# 03-VGA.net
KiCad netlist of a schematic drawn in Altium Designer
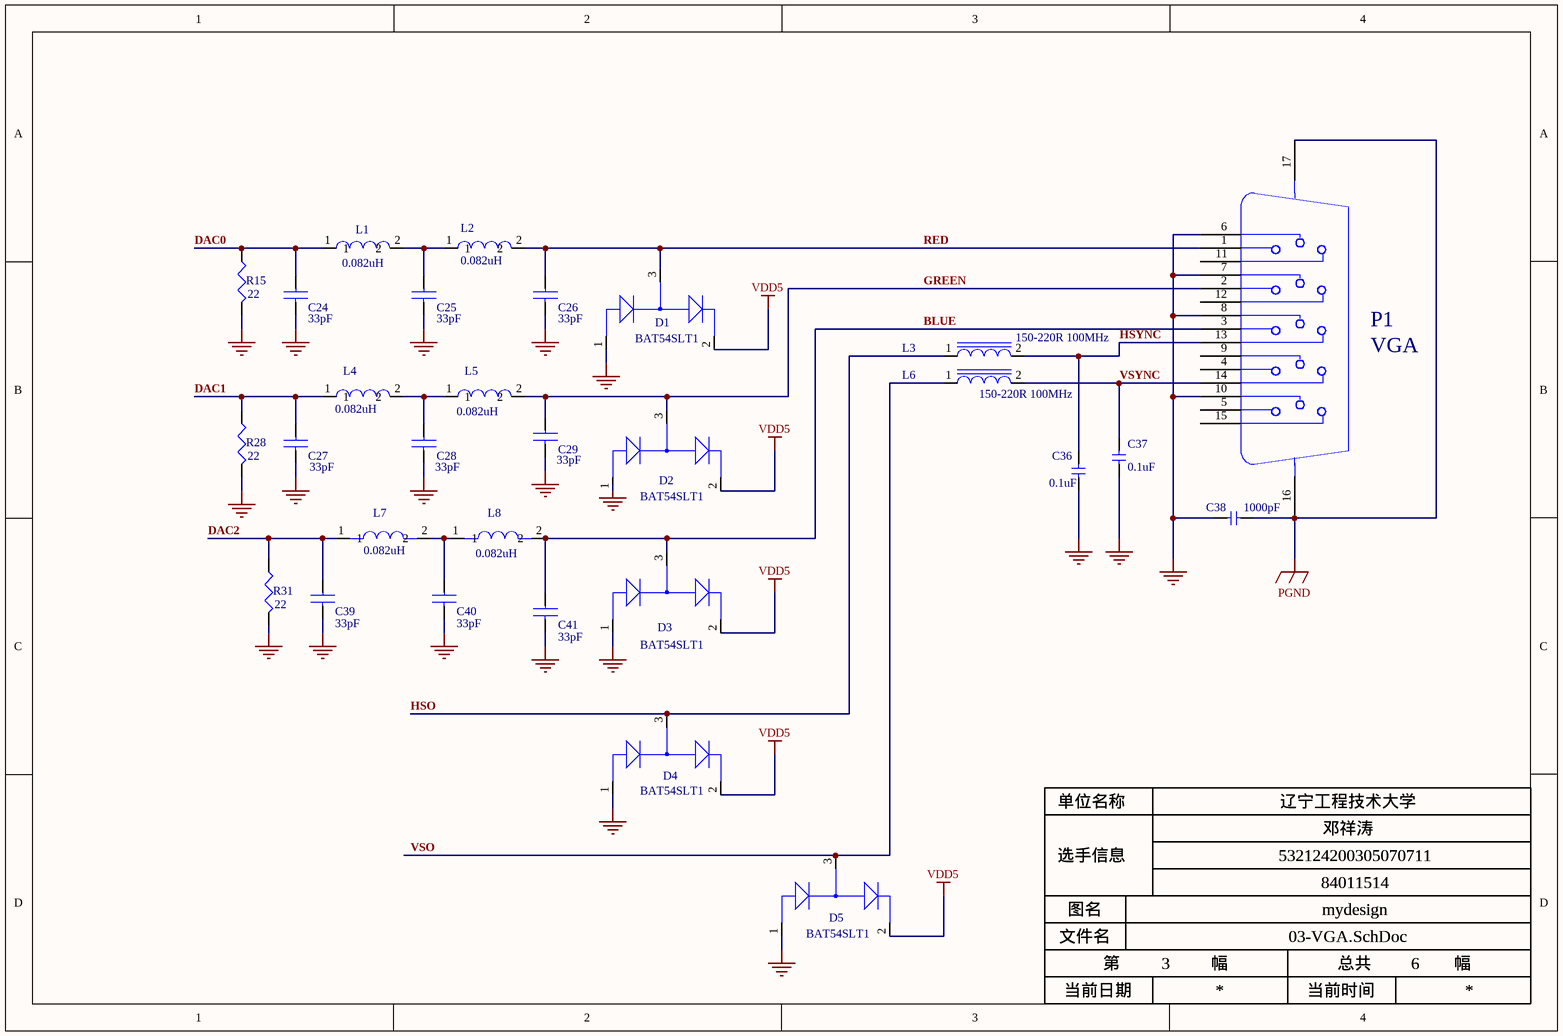
[diagram p0: 03-VGA.SchDoc]

(export (version "E")
  (design (tool "Eeschema 10.0.6"))
  (components
    (comp (ref "C24")
      (value "33pF")
      (footprint "C0603")
      (fields (field (name "Comment") "CAP"))
      (libsource (lib "VIDEO_Demo_Kit_1") (part "CAP"))
    )
    (comp (ref "C25")
      (value "33pF")
      (footprint "C0603")
      (fields (field (name "Comment") "CAP"))
      (libsource (lib "VIDEO_Demo_Kit_1") (part "CAP"))
    )
    (comp (ref "C26")
      (value "33pF")
      (footprint "C0603")
      (fields (field (name "Comment") "CAP"))
      (libsource (lib "VIDEO_Demo_Kit_1") (part "CAP"))
    )
    (comp (ref "C27")
      (value "33pF")
      (footprint "C0603")
      (fields (field (name "Comment") "CAP"))
      (libsource (lib "VIDEO_Demo_Kit_1") (part "CAP"))
    )
    (comp (ref "C28")
      (value "33pF")
      (footprint "C0603")
      (fields (field (name "Comment") "CAP"))
      (libsource (lib "VIDEO_Demo_Kit_1") (part "CAP"))
    )
    (comp (ref "C29")
      (value "33pF")
      (footprint "C0603")
      (fields (field (name "Comment") "CAP"))
      (libsource (lib "VIDEO_Demo_Kit_1") (part "CAP"))
    )
    (comp (ref "C36")
      (value "0.1uF")
      (footprint "C0603")
      (fields (field (name "VOLTAGE") "CMAX") (field (name "Comment") "C_2"))
      (libsource (lib "VIDEO_Demo_Kit_1") (part "C_2"))
    )
    (comp (ref "C37")
      (value "0.1uF")
      (footprint "C0603")
      (fields (field (name "VOLTAGE") "CMAX") (field (name "Comment") "C_2"))
      (libsource (lib "VIDEO_Demo_Kit_1") (part "C_2"))
    )
    (comp (ref "C38")
      (value "1000pF")
      (footprint "C0603")
      (fields (field (name "VOLTAGE") "CMAX") (field (name "Comment") "C_2"))
      (libsource (lib "VIDEO_Demo_Kit_1") (part "C_2"))
    )
    (comp (ref "C39")
      (value "33pF")
      (footprint "C0603")
      (fields (field (name "Comment") "CAP"))
      (libsource (lib "VIDEO_Demo_Kit_1") (part "CAP"))
    )
    (comp (ref "C40")
      (value "33pF")
      (footprint "C0603")
      (fields (field (name "Comment") "CAP"))
      (libsource (lib "VIDEO_Demo_Kit_1") (part "CAP"))
    )
    (comp (ref "C41")
      (value "33pF")
      (footprint "C0603")
      (fields (field (name "Comment") "CAP"))
      (libsource (lib "VIDEO_Demo_Kit_1") (part "CAP"))
    )
    (comp (ref "D1")
      (value "BAT54SLT1")
      (footprint "SOT-23")
      (fields (field (name "Comment") "DIODE_DUAL_SERIES_SOT23"))
      (libsource (lib "VIDEO_Demo_Kit_1") (part "DIODE_DUAL_SERIES_SOT23"))
    )
    (comp (ref "D2")
      (value "BAT54SLT1")
      (footprint "SOT-23")
      (fields (field (name "Comment") "DIODE_DUAL_SERIES_SOT23"))
      (libsource (lib "VIDEO_Demo_Kit_1") (part "DIODE_DUAL_SERIES_SOT23"))
    )
    (comp (ref "D3")
      (value "BAT54SLT1")
      (footprint "SOT-23")
      (fields (field (name "Comment") "DIODE_DUAL_SERIES_SOT23"))
      (libsource (lib "VIDEO_Demo_Kit_1") (part "DIODE_DUAL_SERIES_SOT23"))
    )
    (comp (ref "D4")
      (value "BAT54SLT1")
      (footprint "SOT-23")
      (fields (field (name "Comment") "DIODE_DUAL_SERIES_SOT23"))
      (libsource (lib "VIDEO_Demo_Kit_1") (part "DIODE_DUAL_SERIES_SOT23"))
    )
    (comp (ref "D5")
      (value "BAT54SLT1")
      (footprint "SOT-23")
      (fields (field (name "Comment") "DIODE_DUAL_SERIES_SOT23"))
      (libsource (lib "VIDEO_Demo_Kit_1") (part "DIODE_DUAL_SERIES_SOT23"))
    )
    (comp (ref "L1")
      (value "0.082uH")
      (footprint "0805-l")
      (fields (field (name "Comment") "L"))
      (libsource (lib "*") (part "L"))
    )
    (comp (ref "L2")
      (value "0.082uH")
      (footprint "0805-l")
      (fields (field (name "Comment") "L"))
      (libsource (lib "*") (part "L"))
    )
    (comp (ref "L3")
      (value "150-220R 100MHz")
      (footprint "0805-l")
      (fields (field (name "Comment") "L_0"))
      (libsource (lib "VIDEO_Demo_Kit_1") (part "L_0"))
    )
    (comp (ref "L4")
      (value "0.082uH")
      (footprint "0805-l")
      (fields (field (name "Comment") "L"))
      (libsource (lib "*") (part "L"))
    )
    (comp (ref "L5")
      (value "0.082uH")
      (footprint "0805-l")
      (fields (field (name "Comment") "L"))
      (libsource (lib "*") (part "L"))
    )
    (comp (ref "L6")
      (value "150-220R 100MHz")
      (footprint "0805-l")
      (fields (field (name "Comment") "L_0"))
      (libsource (lib "VIDEO_Demo_Kit_1") (part "L_0"))
    )
    (comp (ref "L7")
      (value "0.082uH")
      (footprint "0805-l")
      (fields (field (name "Comment") "FERRITE_BEAD"))
      (libsource (lib "*") (part "FERRITE_BEAD"))
    )
    (comp (ref "L8")
      (value "0.082uH")
      (footprint "0805-l")
      (fields (field (name "Comment") "FERRITE_BEAD"))
      (libsource (lib "*") (part "FERRITE_BEAD"))
    )
    (comp (ref "P1")
      (value "VGA")
      (footprint "DSUB-15")
      (fields (field (name "Comment") "VGA_5"))
      (libsource (lib "VIDEO_Demo_Kit_1") (part "VGA_5"))
    )
    (comp (ref "R15")
      (value "22")
      (footprint "R0603")
      (fields (field (name "Comment") "RESISTOR_2"))
      (libsource (lib "VIDEO_Demo_Kit_1") (part "RESISTOR_2"))
    )
    (comp (ref "R28")
      (value "22")
      (footprint "R0603")
      (fields (field (name "Comment") "RESISTOR_2"))
      (libsource (lib "VIDEO_Demo_Kit_1") (part "RESISTOR_2"))
    )
    (comp (ref "R31")
      (value "22")
      (footprint "R0603")
      (fields (field (name "Comment") "RESISTOR_2"))
      (libsource (lib "VIDEO_Demo_Kit_1") (part "RESISTOR_2"))
    )
  )
  (nets
    (net (code "1") (name "/BLUE") (class "Default")
      (node (ref "C41") (pin "1") (pinfunction "1_1") (pintype "passive"))
      (node (ref "D3") (pin "3") (pinfunction "SIGNAL_3") (pintype "passive"))
      (node (ref "L8") (pin "2") (pinfunction "2_2") (pintype "passive"))
      (node (ref "P1") (pin "3") (pinfunction "3_3") (pintype "passive"))
    )
    (net (code "2") (name "/DAC0") (class "Default")
      (node (ref "C24") (pin "1") (pinfunction "1_1") (pintype "passive"))
      (node (ref "L1") (pin "1") (pinfunction "1_1") (pintype "passive"))
      (node (ref "R15") (pin "1") (pinfunction "1_1") (pintype "passive"))
    )
    (net (code "3") (name "/DAC1") (class "Default")
      (node (ref "C27") (pin "1") (pinfunction "1_1") (pintype "passive"))
      (node (ref "L4") (pin "1") (pinfunction "1_1") (pintype "passive"))
      (node (ref "R28") (pin "1") (pinfunction "1_1") (pintype "passive"))
    )
    (net (code "4") (name "/DAC2") (class "Default")
      (node (ref "C39") (pin "1") (pinfunction "1_1") (pintype "passive"))
      (node (ref "L7") (pin "1") (pinfunction "1_1") (pintype "passive"))
      (node (ref "R31") (pin "1") (pinfunction "1_1") (pintype "passive"))
    )
    (net (code "5") (name "/GREEN") (class "Default")
      (node (ref "C29") (pin "1") (pinfunction "1_1") (pintype "passive"))
      (node (ref "D2") (pin "3") (pinfunction "SIGNAL_3") (pintype "passive"))
      (node (ref "L5") (pin "2") (pinfunction "2_2") (pintype "passive"))
      (node (ref "P1") (pin "2") (pinfunction "2_2") (pintype "passive"))
    )
    (net (code "6") (name "/HSO") (class "Default")
      (node (ref "D4") (pin "3") (pinfunction "SIGNAL_3") (pintype "passive"))
      (node (ref "L3") (pin "1") (pinfunction "1_1") (pintype "passive"))
    )
    (net (code "7") (name "/HSYNC") (class "Default")
      (node (ref "C36") (pin "2") (pinfunction "2_2") (pintype "passive"))
      (node (ref "L3") (pin "2") (pinfunction "2_2") (pintype "passive"))
      (node (ref "P1") (pin "13") (pinfunction "13_13") (pintype "passive"))
    )
    (net (code "8") (name "/RED") (class "Default")
      (node (ref "C26") (pin "1") (pinfunction "1_1") (pintype "passive"))
      (node (ref "D1") (pin "3") (pinfunction "SIGNAL_3") (pintype "passive"))
      (node (ref "L2") (pin "2") (pinfunction "2_2") (pintype "passive"))
      (node (ref "P1") (pin "1") (pinfunction "1_1") (pintype "passive"))
    )
    (net (code "9") (name "/VSO") (class "Default")
      (node (ref "D5") (pin "3") (pinfunction "SIGNAL_3") (pintype "passive"))
      (node (ref "L6") (pin "1") (pinfunction "1_1") (pintype "passive"))
    )
    (net (code "10") (name "/VSYNC") (class "Default")
      (node (ref "C37") (pin "2") (pinfunction "2_2") (pintype "passive"))
      (node (ref "L6") (pin "2") (pinfunction "2_2") (pintype "passive"))
      (node (ref "P1") (pin "14") (pinfunction "14_14") (pintype "passive"))
    )
    (net (code "11") (name "GND") (class "Default")
      (node (ref "C24") (pin "2") (pinfunction "2_2") (pintype "passive"))
      (node (ref "C25") (pin "2") (pinfunction "2_2") (pintype "passive"))
      (node (ref "C26") (pin "2") (pinfunction "2_2") (pintype "passive"))
      (node (ref "C27") (pin "2") (pinfunction "2_2") (pintype "passive"))
      (node (ref "C28") (pin "2") (pinfunction "2_2") (pintype "passive"))
      (node (ref "C29") (pin "2") (pinfunction "2_2") (pintype "passive"))
      (node (ref "C36") (pin "1") (pinfunction "1_1") (pintype "passive"))
      (node (ref "C37") (pin "1") (pinfunction "1_1") (pintype "passive"))
      (node (ref "C38") (pin "2") (pinfunction "2_2") (pintype "passive"))
      (node (ref "C39") (pin "2") (pinfunction "2_2") (pintype "passive"))
      (node (ref "C40") (pin "2") (pinfunction "2_2") (pintype "passive"))
      (node (ref "C41") (pin "2") (pinfunction "2_2") (pintype "passive"))
      (node (ref "D1") (pin "1") (pinfunction "GND_1") (pintype "passive"))
      (node (ref "D2") (pin "1") (pinfunction "GND_1") (pintype "passive"))
      (node (ref "D3") (pin "1") (pinfunction "GND_1") (pintype "passive"))
      (node (ref "D4") (pin "1") (pinfunction "GND_1") (pintype "passive"))
      (node (ref "D5") (pin "1") (pinfunction "GND_1") (pintype "passive"))
      (node (ref "P1") (pin "10") (pinfunction "10_10") (pintype "passive"))
      (node (ref "P1") (pin "6") (pinfunction "6_6") (pintype "passive"))
      (node (ref "P1") (pin "7") (pinfunction "7_7") (pintype "passive"))
      (node (ref "P1") (pin "8") (pinfunction "8_8") (pintype "passive"))
      (node (ref "R15") (pin "2") (pinfunction "2_2") (pintype "passive"))
      (node (ref "R28") (pin "2") (pinfunction "2_2") (pintype "passive"))
      (node (ref "R31") (pin "2") (pinfunction "2_2") (pintype "passive"))
    )
    (net (code "12") (name "Net-(C25-Pad1)") (class "Default")
      (node (ref "C25") (pin "1") (pinfunction "1_1") (pintype "passive"))
      (node (ref "L1") (pin "2") (pinfunction "2_2") (pintype "passive"))
      (node (ref "L2") (pin "1") (pinfunction "1_1") (pintype "passive"))
    )
    (net (code "13") (name "Net-(C28-Pad1)") (class "Default")
      (node (ref "C28") (pin "1") (pinfunction "1_1") (pintype "passive"))
      (node (ref "L4") (pin "2") (pinfunction "2_2") (pintype "passive"))
      (node (ref "L5") (pin "1") (pinfunction "1_1") (pintype "passive"))
    )
    (net (code "14") (name "Net-(C40-Pad1)") (class "Default")
      (node (ref "C40") (pin "1") (pinfunction "1_1") (pintype "passive"))
      (node (ref "L7") (pin "2") (pinfunction "2_2") (pintype "passive"))
      (node (ref "L8") (pin "1") (pinfunction "1_1") (pintype "passive"))
    )
    (net (code "15") (name "PGND") (class "Default")
      (node (ref "C38") (pin "1") (pinfunction "1_1") (pintype "passive"))
      (node (ref "P1") (pin "16") (pinfunction "16_16") (pintype "passive"))
      (node (ref "P1") (pin "17") (pinfunction "17_17") (pintype "passive"))
    )
    (net (code "16") (name "VDD5") (class "Default")
      (node (ref "D1") (pin "2") (pinfunction "VDD_2") (pintype "passive"))
      (node (ref "D2") (pin "2") (pinfunction "VDD_2") (pintype "passive"))
      (node (ref "D3") (pin "2") (pinfunction "VDD_2") (pintype "passive"))
      (node (ref "D4") (pin "2") (pinfunction "VDD_2") (pintype "passive"))
      (node (ref "D5") (pin "2") (pinfunction "VDD_2") (pintype "passive"))
    )
    (net (code "17") (name "unconnected-(P1-Pad4)") (class "Default")
      (node (ref "P1") (pin "4") (pinfunction "4_4") (pintype "passive"))
    )
    (net (code "18") (name "unconnected-(P1-Pad5)") (class "Default")
      (node (ref "P1") (pin "5") (pinfunction "5_5") (pintype "passive"))
    )
    (net (code "19") (name "unconnected-(P1-Pad9)") (class "Default")
      (node (ref "P1") (pin "9") (pinfunction "9_9") (pintype "passive"))
    )
    (net (code "20") (name "unconnected-(P1-Pad11)") (class "Default")
      (node (ref "P1") (pin "11") (pinfunction "11_11") (pintype "passive"))
    )
    (net (code "21") (name "unconnected-(P1-Pad12)") (class "Default")
      (node (ref "P1") (pin "12") (pinfunction "12_12") (pintype "passive"))
    )
    (net (code "22") (name "unconnected-(P1-Pad15)") (class "Default")
      (node (ref "P1") (pin "15") (pinfunction "15_15") (pintype "passive"))
    )
  )
)
